# logic6_main.net
KiCad netlist of a schematic drawn in Altium Designer
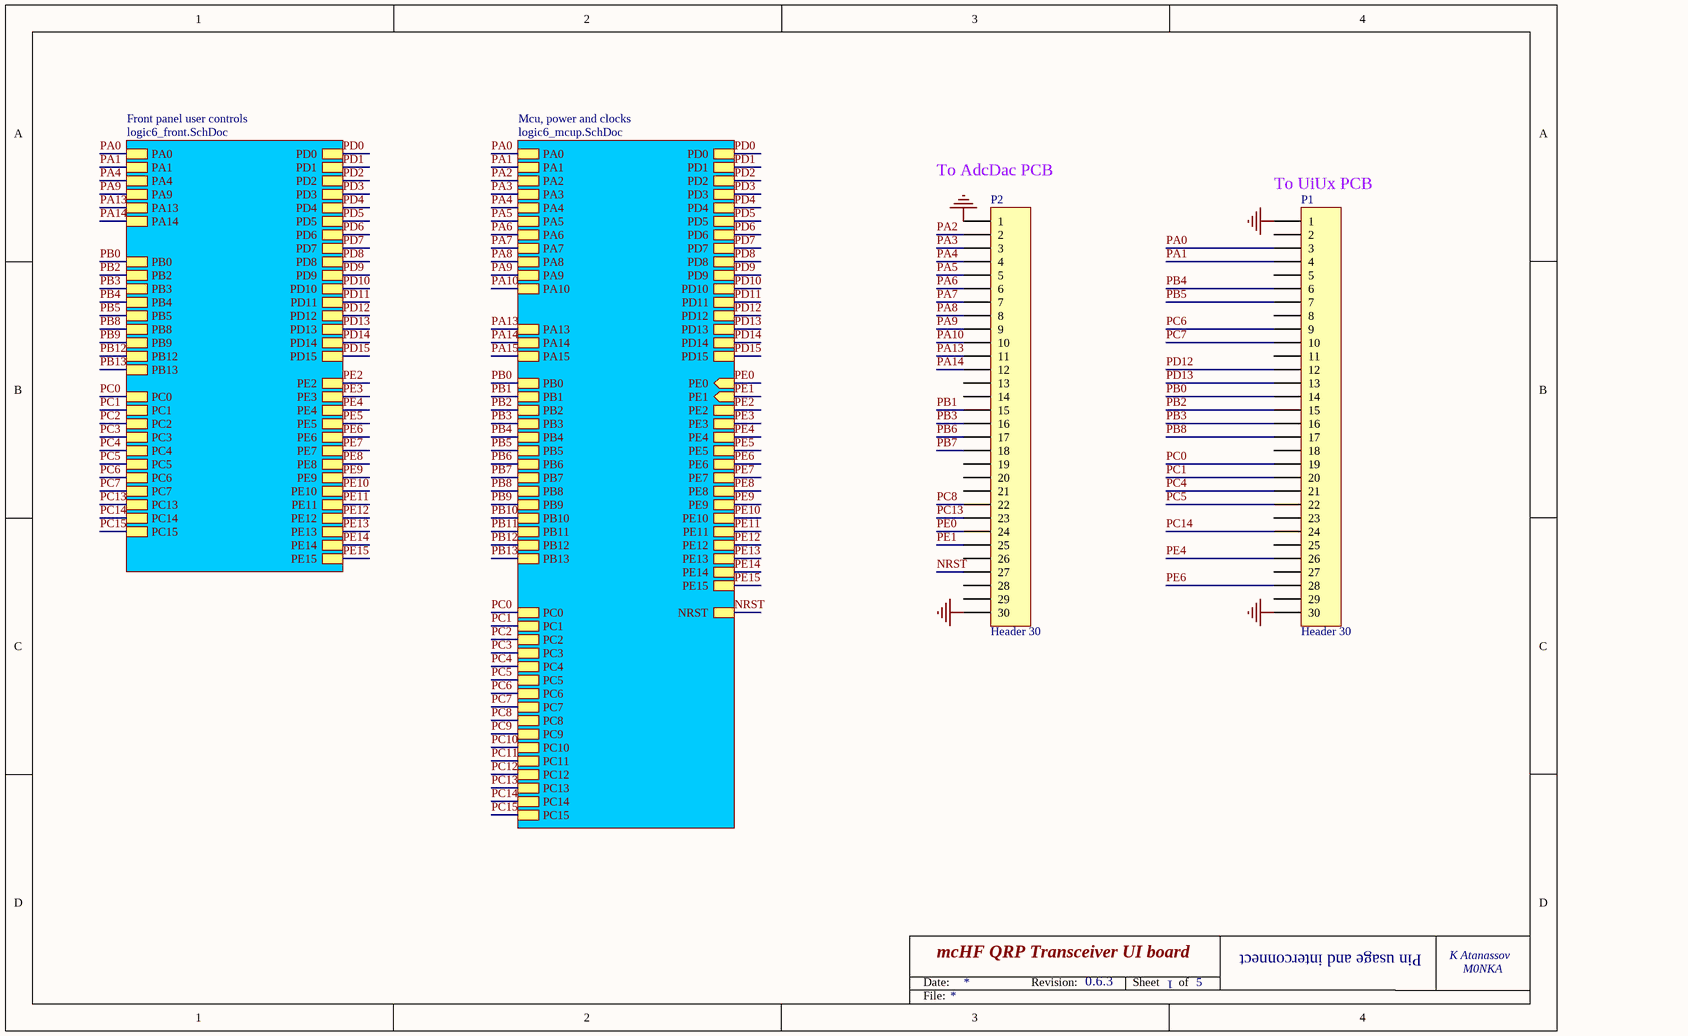
[diagram p0: logic6_main.SchDoc]

(export (version "E")
  (design (tool "Eeschema 10.0.6"))
  (components
    (comp (ref "P1")
      (value "Header 30")
      (footprint "HDR1X30")
      (description "Header, 30-Pin")
      (libsource (lib "mcHF_ui") (part "Header 30"))
    )
    (comp (ref "P2")
      (value "Header 30")
      (footprint "HDR1X30")
      (description "Header, 30-Pin")
      (libsource (lib "mcHF_ui") (part "Header 30"))
    )
  )
  (nets
    (net (code "1") (name "/NRST") (class "Default")
      (node (ref "P2") (pin "27") (pinfunction "27_27") (pintype "passive"))
    )
    (net (code "2") (name "/PA0") (class "Default")
      (node (ref "P1") (pin "3") (pinfunction "3_3") (pintype "passive"))
    )
    (net (code "3") (name "/PA1") (class "Default")
      (node (ref "P1") (pin "4") (pinfunction "4_4") (pintype "passive"))
    )
    (net (code "4") (name "/PA2") (class "Default")
      (node (ref "P2") (pin "2") (pinfunction "2_2") (pintype "passive"))
    )
    (net (code "5") (name "/PA3") (class "Default")
      (node (ref "P2") (pin "3") (pinfunction "3_3") (pintype "passive"))
    )
    (net (code "6") (name "/PA4") (class "Default")
      (node (ref "P2") (pin "4") (pinfunction "4_4") (pintype "passive"))
    )
    (net (code "7") (name "/PA5") (class "Default")
      (node (ref "P2") (pin "5") (pinfunction "5_5") (pintype "passive"))
    )
    (net (code "8") (name "/PA6") (class "Default")
      (node (ref "P2") (pin "6") (pinfunction "6_6") (pintype "passive"))
    )
    (net (code "9") (name "/PA7") (class "Default")
      (node (ref "P2") (pin "7") (pinfunction "7_7") (pintype "passive"))
    )
    (net (code "10") (name "/PA8") (class "Default")
      (node (ref "P2") (pin "8") (pinfunction "8_8") (pintype "passive"))
    )
    (net (code "11") (name "/PA9") (class "Default")
      (node (ref "P2") (pin "9") (pinfunction "9_9") (pintype "passive"))
    )
    (net (code "12") (name "/PA10") (class "Default")
      (node (ref "P2") (pin "10") (pinfunction "10_10") (pintype "passive"))
    )
    (net (code "13") (name "/PA13") (class "Default")
      (node (ref "P2") (pin "11") (pinfunction "11_11") (pintype "passive"))
    )
    (net (code "14") (name "/PA14") (class "Default")
      (node (ref "P2") (pin "12") (pinfunction "12_12") (pintype "passive"))
    )
    (net (code "16") (name "/PB0") (class "Default")
      (node (ref "P1") (pin "14") (pinfunction "14_14") (pintype "passive"))
    )
    (net (code "17") (name "/PB1") (class "Default")
      (node (ref "P2") (pin "15") (pinfunction "15_15") (pintype "passive"))
    )
    (net (code "18") (name "/PB2") (class "Default")
      (node (ref "P1") (pin "15") (pinfunction "15_15") (pintype "passive"))
    )
    (net (code "19") (name "/PB3") (class "Default")
      (node (ref "P1") (pin "16") (pinfunction "16_16") (pintype "passive"))
      (node (ref "P2") (pin "16") (pinfunction "16_16") (pintype "passive"))
    )
    (net (code "20") (name "/PB4") (class "Default")
      (node (ref "P1") (pin "6") (pinfunction "6_6") (pintype "passive"))
    )
    (net (code "21") (name "/PB5") (class "Default")
      (node (ref "P1") (pin "7") (pinfunction "7_7") (pintype "passive"))
    )
    (net (code "22") (name "/PB6") (class "Default")
      (node (ref "P2") (pin "17") (pinfunction "17_17") (pintype "passive"))
    )
    (net (code "23") (name "/PB7") (class "Default")
      (node (ref "P2") (pin "18") (pinfunction "18_18") (pintype "passive"))
    )
    (net (code "24") (name "/PB8") (class "Default")
      (node (ref "P1") (pin "17") (pinfunction "17_17") (pintype "passive"))
    )
    (net (code "30") (name "/PC0") (class "Default")
      (node (ref "P1") (pin "19") (pinfunction "19_19") (pintype "passive"))
    )
    (net (code "31") (name "/PC1") (class "Default")
      (node (ref "P1") (pin "20") (pinfunction "20_20") (pintype "passive"))
    )
    (net (code "34") (name "/PC4") (class "Default")
      (node (ref "P1") (pin "21") (pinfunction "21_21") (pintype "passive"))
    )
    (net (code "35") (name "/PC5") (class "Default")
      (node (ref "P1") (pin "22") (pinfunction "22_22") (pintype "passive"))
    )
    (net (code "36") (name "/PC6") (class "Default")
      (node (ref "P1") (pin "9") (pinfunction "9_9") (pintype "passive"))
    )
    (net (code "37") (name "/PC7") (class "Default")
      (node (ref "P1") (pin "10") (pinfunction "10_10") (pintype "passive"))
    )
    (net (code "38") (name "/PC8") (class "Default")
      (node (ref "P2") (pin "22") (pinfunction "22_22") (pintype "passive"))
    )
    (net (code "43") (name "/PC13") (class "Default")
      (node (ref "P2") (pin "23") (pinfunction "23_23") (pintype "passive"))
    )
    (net (code "44") (name "/PC14") (class "Default")
      (node (ref "P1") (pin "24") (pinfunction "24_24") (pintype "passive"))
    )
    (net (code "58") (name "/PD12") (class "Default")
      (node (ref "P1") (pin "12") (pinfunction "12_12") (pintype "passive"))
    )
    (net (code "59") (name "/PD13") (class "Default")
      (node (ref "P1") (pin "13") (pinfunction "13_13") (pintype "passive"))
    )
    (net (code "62") (name "/PE0") (class "Default")
      (node (ref "P2") (pin "24") (pinfunction "24_24") (pintype "passive"))
    )
    (net (code "63") (name "/PE1") (class "Default")
      (node (ref "P2") (pin "25") (pinfunction "25_25") (pintype "passive"))
    )
    (net (code "66") (name "/PE4") (class "Default")
      (node (ref "P1") (pin "26") (pinfunction "26_26") (pintype "passive"))
    )
    (net (code "68") (name "/PE6") (class "Default")
      (node (ref "P1") (pin "28") (pinfunction "28_28") (pintype "passive"))
    )
    (net (code "78") (name "GND") (class "Default")
      (node (ref "P1") (pin "1") (pinfunction "1_1") (pintype "passive"))
      (node (ref "P1") (pin "30") (pinfunction "30_30") (pintype "passive"))
      (node (ref "P2") (pin "1") (pinfunction "1_1") (pintype "passive"))
      (node (ref "P2") (pin "30") (pinfunction "30_30") (pintype "passive"))
    )
    (net (code "79") (name "unconnected-(P1-Pad2)") (class "Default")
      (node (ref "P1") (pin "2") (pinfunction "2_2") (pintype "passive"))
    )
    (net (code "80") (name "unconnected-(P1-Pad5)") (class "Default")
      (node (ref "P1") (pin "5") (pinfunction "5_5") (pintype "passive"))
    )
    (net (code "81") (name "unconnected-(P1-Pad8)") (class "Default")
      (node (ref "P1") (pin "8") (pinfunction "8_8") (pintype "passive"))
    )
    (net (code "82") (name "unconnected-(P1-Pad11)") (class "Default")
      (node (ref "P1") (pin "11") (pinfunction "11_11") (pintype "passive"))
    )
    (net (code "83") (name "unconnected-(P1-Pad18)") (class "Default")
      (node (ref "P1") (pin "18") (pinfunction "18_18") (pintype "passive"))
    )
    (net (code "84") (name "unconnected-(P1-Pad23)") (class "Default")
      (node (ref "P1") (pin "23") (pinfunction "23_23") (pintype "passive"))
    )
    (net (code "85") (name "unconnected-(P1-Pad25)") (class "Default")
      (node (ref "P1") (pin "25") (pinfunction "25_25") (pintype "passive"))
    )
    (net (code "86") (name "unconnected-(P1-Pad27)") (class "Default")
      (node (ref "P1") (pin "27") (pinfunction "27_27") (pintype "passive"))
    )
    (net (code "87") (name "unconnected-(P1-Pad29)") (class "Default")
      (node (ref "P1") (pin "29") (pinfunction "29_29") (pintype "passive"))
    )
    (net (code "88") (name "unconnected-(P2-Pad13)") (class "Default")
      (node (ref "P2") (pin "13") (pinfunction "13_13") (pintype "passive"))
    )
    (net (code "89") (name "unconnected-(P2-Pad14)") (class "Default")
      (node (ref "P2") (pin "14") (pinfunction "14_14") (pintype "passive"))
    )
    (net (code "90") (name "unconnected-(P2-Pad19)") (class "Default")
      (node (ref "P2") (pin "19") (pinfunction "19_19") (pintype "passive"))
    )
    (net (code "91") (name "unconnected-(P2-Pad20)") (class "Default")
      (node (ref "P2") (pin "20") (pinfunction "20_20") (pintype "passive"))
    )
    (net (code "92") (name "unconnected-(P2-Pad21)") (class "Default")
      (node (ref "P2") (pin "21") (pinfunction "21_21") (pintype "passive"))
    )
    (net (code "93") (name "unconnected-(P2-Pad26)") (class "Default")
      (node (ref "P2") (pin "26") (pinfunction "26_26") (pintype "passive"))
    )
    (net (code "94") (name "unconnected-(P2-Pad28)") (class "Default")
      (node (ref "P2") (pin "28") (pinfunction "28_28") (pintype "passive"))
    )
    (net (code "95") (name "unconnected-(P2-Pad29)") (class "Default")
      (node (ref "P2") (pin "29") (pinfunction "29_29") (pintype "passive"))
    )
  )
)
